# soraduino_lite.net
KiCad netlist of a schematic drawn in EAGLE
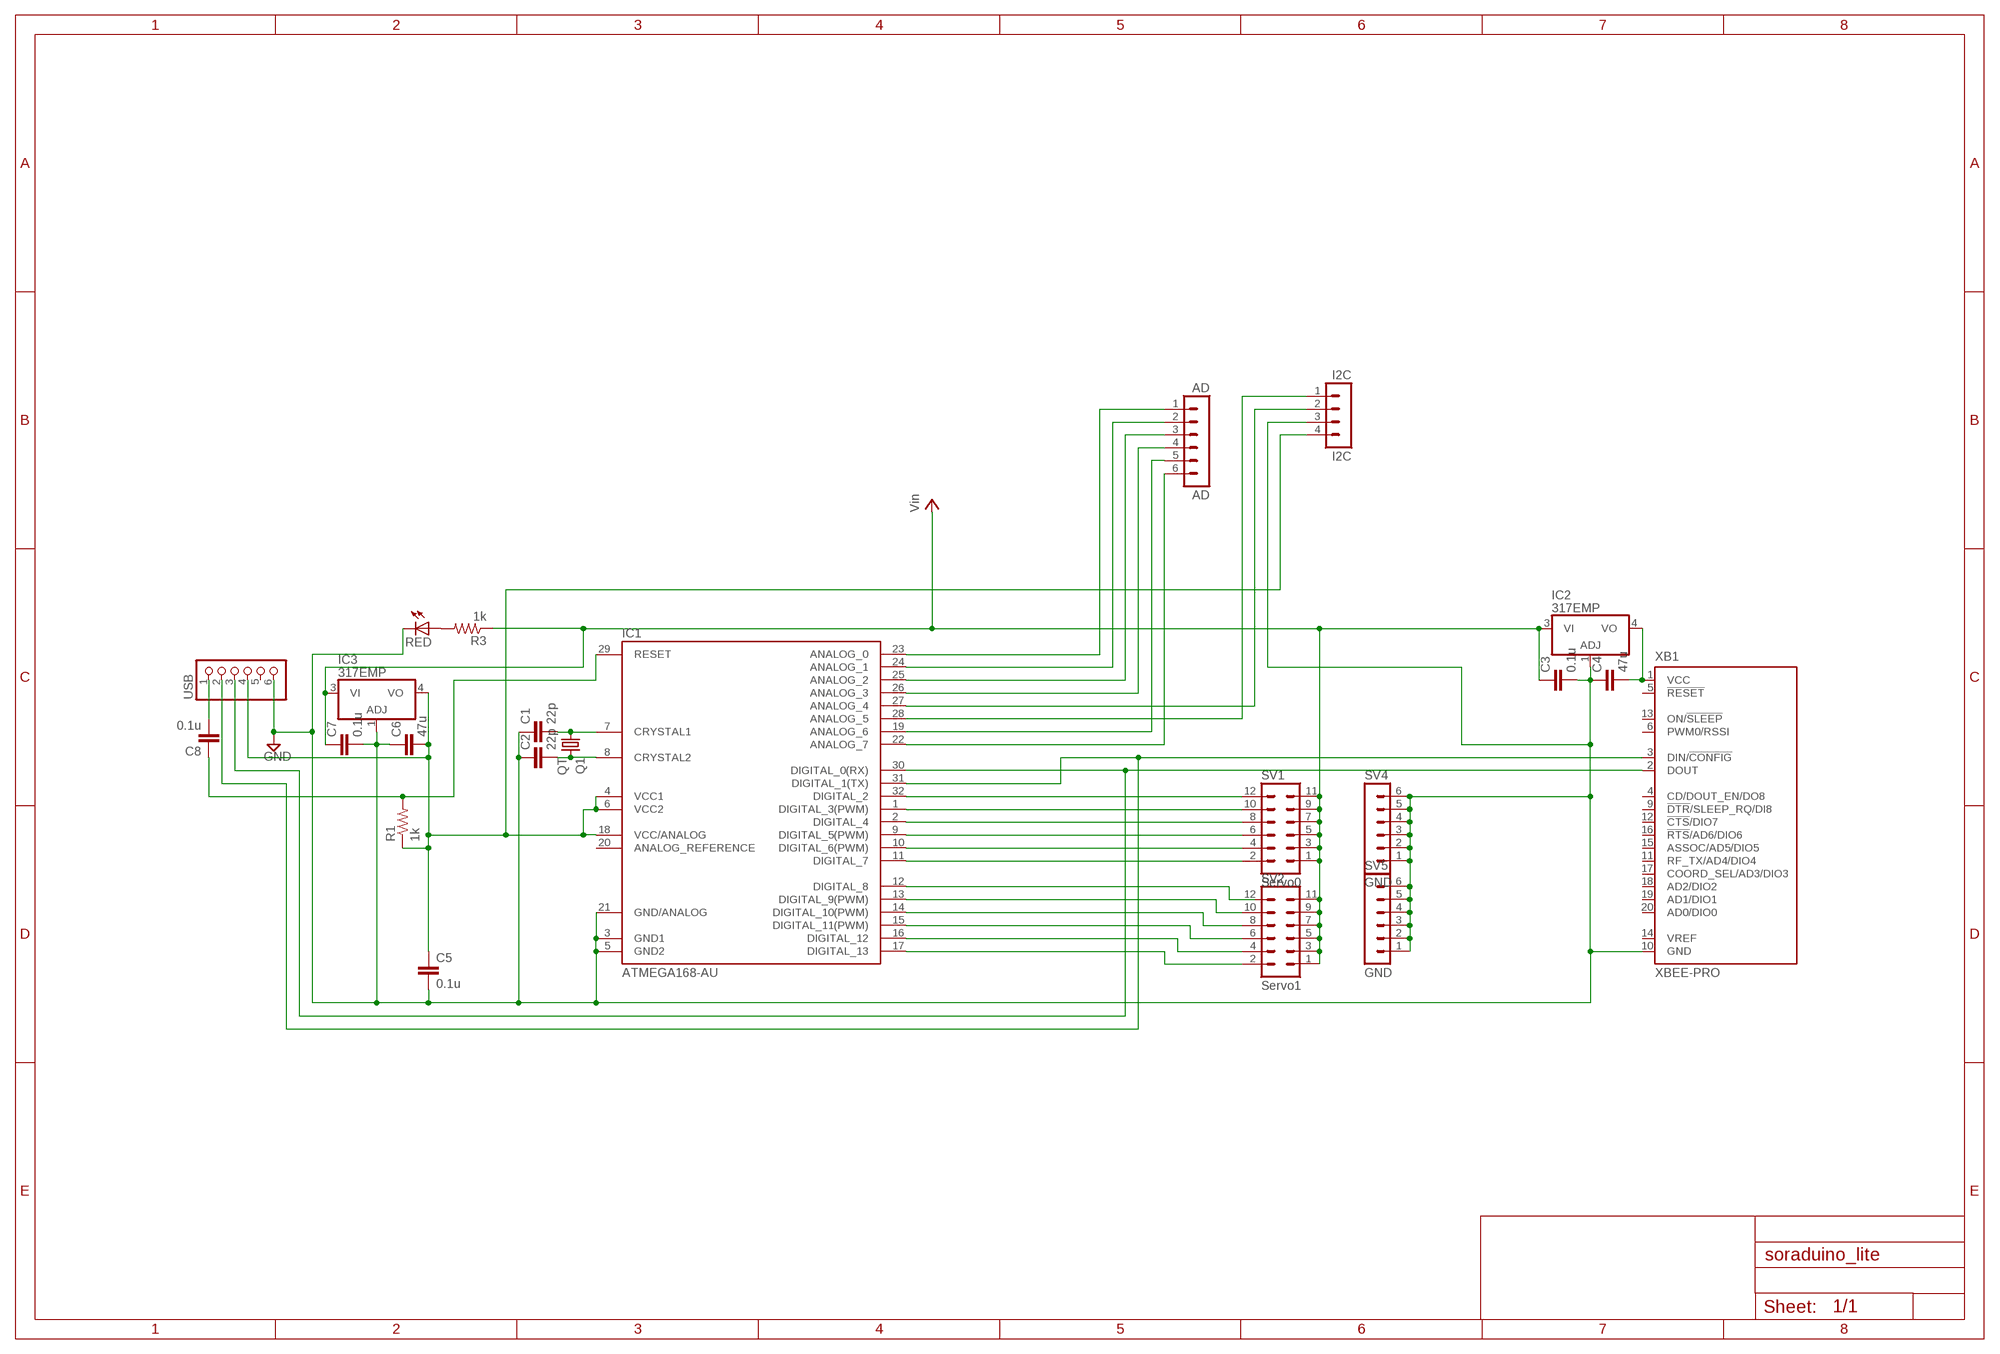
[diagram p0: schematic, sheet 1]

(export (version "E")
  (design (tool "Eeschema 10.0.6"))
  (components
    (comp (ref "AD")
      (value "AD")
      (footprint "eagle-import:MA06-1")
      (libsource (lib "eagle-import") (part "MA06-1"))
    )
    (comp (ref "C1")
      (value "22p")
      (footprint "eagle-import:C050-024X044")
      (libsource (lib "eagle-import") (part "C-EU050-024X044"))
    )
    (comp (ref "C2")
      (value "22p")
      (footprint "eagle-import:C050-024X044")
      (libsource (lib "eagle-import") (part "C-EU050-024X044"))
    )
    (comp (ref "C3")
      (value "0.1u")
      (footprint "eagle-import:C0805K")
      (libsource (lib "eagle-import") (part "resistor_C-EUC0805K"))
    )
    (comp (ref "C4")
      (value "47u")
      (footprint "eagle-import:C0805K")
      (libsource (lib "eagle-import") (part "resistor_C-EUC0805K"))
    )
    (comp (ref "C5")
      (value "0.1u")
      (footprint "eagle-import:C0805K")
      (libsource (lib "eagle-import") (part "resistor_C-EUC0805K"))
    )
    (comp (ref "C6")
      (value "47u")
      (footprint "eagle-import:C0805K")
      (libsource (lib "eagle-import") (part "resistor_C-EUC0805K"))
    )
    (comp (ref "C7")
      (value "0.1u")
      (footprint "eagle-import:C0805K")
      (libsource (lib "eagle-import") (part "resistor_C-EUC0805K"))
    )
    (comp (ref "C8")
      (value "0.1u")
      (footprint "eagle-import:C0805K")
      (libsource (lib "eagle-import") (part "resistor_C-EUC0805K"))
    )
    (comp (ref "I2C")
      (value "I2C")
      (footprint "eagle-import:MA04-1")
      (libsource (lib "eagle-import") (part "MA04-1"))
    )
    (comp (ref "IC1")
      (value "ATMEGA168-AU")
      (footprint "eagle-import:TQFP32-08")
      (libsource (lib "eagle-import") (part "ATMEGA168-AU"))
    )
    (comp (ref "IC2")
      (value "317EMP")
      (footprint "eagle-import:SOT223")
      (libsource (lib "eagle-import") (part "317EMP"))
    )
    (comp (ref "IC3")
      (value "317EMP")
      (footprint "eagle-import:SOT223")
      (libsource (lib "eagle-import") (part "317EMP"))
    )
    (comp (ref "Q1")
      (value "QT")
      (footprint "eagle-import:HC49_S")
      (libsource (lib "eagle-import") (part "CRYSTALHC49S"))
    )
    (comp (ref "R1")
      (value "1k")
      (footprint "eagle-import:R0603")
      (libsource (lib "eagle-import") (part "R-US_R0603"))
    )
    (comp (ref "R3")
      (value "1k")
      (footprint "eagle-import:R0603")
      (libsource (lib "eagle-import") (part "R-US_R0603"))
    )
    (comp (ref "RED")
      (value "LEDCHIPLED_1206")
      (footprint "eagle-import:CHIPLED_1206")
      (libsource (lib "eagle-import") (part "LEDCHIPLED_1206"))
    )
    (comp (ref "SV1")
      (value "Servo0")
      (footprint "eagle-import:MA06-2")
      (libsource (lib "eagle-import") (part "MA06-2"))
    )
    (comp (ref "SV2")
      (value "Servo1")
      (footprint "eagle-import:MA06-2")
      (libsource (lib "eagle-import") (part "MA06-2"))
    )
    (comp (ref "SV4")
      (value "GND")
      (footprint "eagle-import:MA06-1")
      (libsource (lib "eagle-import") (part "MA06-1"))
    )
    (comp (ref "SV5")
      (value "GND")
      (footprint "eagle-import:MA06-1")
      (libsource (lib "eagle-import") (part "MA06-1"))
    )
    (comp (ref "USB")
      (value "PINHD-1X6")
      (footprint "eagle-import:1X06")
      (libsource (lib "eagle-import") (part "PINHD-1X6"))
    )
    (comp (ref "XB1")
      (value "XBEE-PRO")
      (footprint "eagle-import:XBEE-PRO")
      (fields (field (name "MPN") "XBP24-AWI-001"))
      (libsource (lib "eagle-import") (part "XBEE-PRO"))
    )
  )
  (nets
    (net (code "1") (name "GND") (class "Default")
      (node (ref "C1") (pin "1") (pinfunction "1_1") (pintype "passive"))
      (node (ref "C2") (pin "1") (pinfunction "1_1") (pintype "passive"))
      (node (ref "C3") (pin "2") (pinfunction "2_2") (pintype "passive"))
      (node (ref "C4") (pin "1") (pinfunction "1_1") (pintype "passive"))
      (node (ref "C5") (pin "2") (pinfunction "2_2") (pintype "passive"))
      (node (ref "C6") (pin "1") (pinfunction "1_1") (pintype "passive"))
      (node (ref "C7") (pin "2") (pinfunction "2_2") (pintype "passive"))
      (node (ref "I2C") (pin "3") (pinfunction "3_3") (pintype "passive"))
      (node (ref "IC1") (pin "21") (pinfunction "GND/ANALOG_21") (pintype "power_in"))
      (node (ref "IC1") (pin "3") (pinfunction "GND1_3") (pintype "power_in"))
      (node (ref "IC1") (pin "5") (pinfunction "GND2_5") (pintype "power_in"))
      (node (ref "IC2") (pin "1") (pinfunction "ADJ_1") (pintype "input"))
      (node (ref "IC3") (pin "1") (pinfunction "ADJ_1") (pintype "input"))
      (node (ref "RED") (pin "C") (pinfunction "C_C") (pintype "passive"))
      (node (ref "SV4") (pin "1") (pinfunction "1_1") (pintype "passive"))
      (node (ref "SV4") (pin "2") (pinfunction "2_2") (pintype "passive"))
      (node (ref "SV4") (pin "3") (pinfunction "3_3") (pintype "passive"))
      (node (ref "SV4") (pin "4") (pinfunction "4_4") (pintype "passive"))
      (node (ref "SV4") (pin "5") (pinfunction "5_5") (pintype "passive"))
      (node (ref "SV4") (pin "6") (pinfunction "6_6") (pintype "passive"))
      (node (ref "SV5") (pin "1") (pinfunction "1_1") (pintype "passive"))
      (node (ref "SV5") (pin "2") (pinfunction "2_2") (pintype "passive"))
      (node (ref "SV5") (pin "3") (pinfunction "3_3") (pintype "passive"))
      (node (ref "SV5") (pin "4") (pinfunction "4_4") (pintype "passive"))
      (node (ref "SV5") (pin "5") (pinfunction "5_5") (pintype "passive"))
      (node (ref "SV5") (pin "6") (pinfunction "6_6") (pintype "passive"))
      (node (ref "USB") (pin "6") (pinfunction "6_6") (pintype "passive"))
      (node (ref "XB1") (pin "10") (pinfunction "GND_10") (pintype "power_in"))
    )
    (net (code "2") (name "Net-(C8-Pad2)") (class "Default")
      (node (ref "C8") (pin "2") (pinfunction "2_2") (pintype "passive"))
      (node (ref "USB") (pin "1") (pinfunction "1_1") (pintype "passive"))
    )
    (net (code "3") (name "Net-(IC1-ANALOG_0)") (class "Default")
      (node (ref "AD") (pin "1") (pinfunction "1_1") (pintype "passive"))
      (node (ref "IC1") (pin "23") (pinfunction "ANALOG_0_23") (pintype "bidirectional"))
    )
    (net (code "4") (name "Net-(IC1-ANALOG_1)") (class "Default")
      (node (ref "AD") (pin "2") (pinfunction "2_2") (pintype "passive"))
      (node (ref "IC1") (pin "24") (pinfunction "ANALOG_1_24") (pintype "bidirectional"))
    )
    (net (code "5") (name "Net-(IC1-ANALOG_2)") (class "Default")
      (node (ref "AD") (pin "3") (pinfunction "3_3") (pintype "passive"))
      (node (ref "IC1") (pin "25") (pinfunction "ANALOG_2_25") (pintype "bidirectional"))
    )
    (net (code "6") (name "Net-(IC1-ANALOG_3)") (class "Default")
      (node (ref "AD") (pin "4") (pinfunction "4_4") (pintype "passive"))
      (node (ref "IC1") (pin "26") (pinfunction "ANALOG_3_26") (pintype "bidirectional"))
    )
    (net (code "7") (name "Net-(IC1-ANALOG_4)") (class "Default")
      (node (ref "I2C") (pin "2") (pinfunction "2_2") (pintype "passive"))
      (node (ref "IC1") (pin "27") (pinfunction "ANALOG_4_27") (pintype "bidirectional"))
    )
    (net (code "8") (name "Net-(IC1-ANALOG_5)") (class "Default")
      (node (ref "I2C") (pin "1") (pinfunction "1_1") (pintype "passive"))
      (node (ref "IC1") (pin "28") (pinfunction "ANALOG_5_28") (pintype "bidirectional"))
    )
    (net (code "9") (name "Net-(IC1-ANALOG_6)") (class "Default")
      (node (ref "AD") (pin "5") (pinfunction "5_5") (pintype "passive"))
      (node (ref "IC1") (pin "19") (pinfunction "ANALOG_6_19") (pintype "passive"))
    )
    (net (code "10") (name "Net-(IC1-ANALOG_7)") (class "Default")
      (node (ref "AD") (pin "6") (pinfunction "6_6") (pintype "passive"))
      (node (ref "IC1") (pin "22") (pinfunction "ANALOG_7_22") (pintype "passive"))
    )
    (net (code "11") (name "Net-(IC1-CRYSTAL1)") (class "Default")
      (node (ref "C1") (pin "2") (pinfunction "2_2") (pintype "passive"))
      (node (ref "IC1") (pin "7") (pinfunction "CRYSTAL1_7") (pintype "bidirectional"))
      (node (ref "Q1") (pin "1") (pinfunction "1_1") (pintype "passive"))
    )
    (net (code "12") (name "Net-(IC1-CRYSTAL2)") (class "Default")
      (node (ref "C2") (pin "2") (pinfunction "2_2") (pintype "passive"))
      (node (ref "IC1") (pin "8") (pinfunction "CRYSTAL2_8") (pintype "bidirectional"))
      (node (ref "Q1") (pin "2") (pinfunction "2_2") (pintype "passive"))
    )
    (net (code "13") (name "Net-(IC1-DIGITAL_0(RX))") (class "Default")
      (node (ref "IC1") (pin "30") (pinfunction "DIGITAL_0(RX)_30") (pintype "bidirectional"))
      (node (ref "USB") (pin "3") (pinfunction "3_3") (pintype "passive"))
      (node (ref "XB1") (pin "2") (pinfunction "DOUT_2") (pintype "output"))
    )
    (net (code "14") (name "Net-(IC1-DIGITAL_1(TX))") (class "Default")
      (node (ref "IC1") (pin "31") (pinfunction "DIGITAL_1(TX)_31") (pintype "bidirectional"))
      (node (ref "USB") (pin "2") (pinfunction "2_2") (pintype "passive"))
      (node (ref "XB1") (pin "3") (pinfunction "DIN/~{CONFIG}_3") (pintype "input"))
    )
    (net (code "15") (name "Net-(IC1-DIGITAL_2)") (class "Default")
      (node (ref "IC1") (pin "32") (pinfunction "DIGITAL_2_32") (pintype "bidirectional"))
      (node (ref "SV1") (pin "12") (pinfunction "12_12") (pintype "passive"))
    )
    (net (code "16") (name "Net-(IC1-DIGITAL_3(PWM))") (class "Default")
      (node (ref "IC1") (pin "1") (pinfunction "DIGITAL_3(PWM)_1") (pintype "bidirectional"))
      (node (ref "SV1") (pin "10") (pinfunction "10_10") (pintype "passive"))
    )
    (net (code "17") (name "Net-(IC1-DIGITAL_4)") (class "Default")
      (node (ref "IC1") (pin "2") (pinfunction "DIGITAL_4_2") (pintype "bidirectional"))
      (node (ref "SV1") (pin "8") (pinfunction "8_8") (pintype "passive"))
    )
    (net (code "18") (name "Net-(IC1-DIGITAL_5(PWM))") (class "Default")
      (node (ref "IC1") (pin "9") (pinfunction "DIGITAL_5(PWM)_9") (pintype "bidirectional"))
      (node (ref "SV1") (pin "6") (pinfunction "6_6") (pintype "passive"))
    )
    (net (code "19") (name "Net-(IC1-DIGITAL_6(PWM))") (class "Default")
      (node (ref "IC1") (pin "10") (pinfunction "DIGITAL_6(PWM)_10") (pintype "bidirectional"))
      (node (ref "SV1") (pin "4") (pinfunction "4_4") (pintype "passive"))
    )
    (net (code "20") (name "Net-(IC1-DIGITAL_7)") (class "Default")
      (node (ref "IC1") (pin "11") (pinfunction "DIGITAL_7_11") (pintype "bidirectional"))
      (node (ref "SV1") (pin "2") (pinfunction "2_2") (pintype "passive"))
    )
    (net (code "21") (name "Net-(IC1-DIGITAL_9(PWM))") (class "Default")
      (node (ref "IC1") (pin "13") (pinfunction "DIGITAL_9(PWM)_13") (pintype "bidirectional"))
      (node (ref "SV2") (pin "10") (pinfunction "10_10") (pintype "passive"))
    )
    (net (code "22") (name "Net-(IC1-DIGITAL_10(PWM))") (class "Default")
      (node (ref "IC1") (pin "14") (pinfunction "DIGITAL_10(PWM)_14") (pintype "bidirectional"))
      (node (ref "SV2") (pin "8") (pinfunction "8_8") (pintype "passive"))
    )
    (net (code "23") (name "Net-(IC1-DIGITAL_11(PWM))") (class "Default")
      (node (ref "IC1") (pin "15") (pinfunction "DIGITAL_11(PWM)_15") (pintype "bidirectional"))
      (node (ref "SV2") (pin "6") (pinfunction "6_6") (pintype "passive"))
    )
    (net (code "24") (name "Net-(IC1-DIGITAL_12)") (class "Default")
      (node (ref "IC1") (pin "16") (pinfunction "DIGITAL_12_16") (pintype "bidirectional"))
      (node (ref "SV2") (pin "4") (pinfunction "4_4") (pintype "passive"))
    )
    (net (code "25") (name "Net-(IC1-DIGITAL_13)") (class "Default")
      (node (ref "IC1") (pin "17") (pinfunction "DIGITAL_13_17") (pintype "bidirectional"))
      (node (ref "SV2") (pin "2") (pinfunction "2_2") (pintype "passive"))
    )
    (net (code "26") (name "Net-(IC1-RESET)") (class "Default")
      (node (ref "C8") (pin "1") (pinfunction "1_1") (pintype "passive"))
      (node (ref "IC1") (pin "29") (pinfunction "RESET_29") (pintype "bidirectional"))
      (node (ref "R1") (pin "2") (pinfunction "2_2") (pintype "passive"))
    )
    (net (code "27") (name "Net-(IC1-VCC1)") (class "Default")
      (node (ref "C5") (pin "1") (pinfunction "1_1") (pintype "passive"))
      (node (ref "C6") (pin "2") (pinfunction "2_2") (pintype "passive"))
      (node (ref "I2C") (pin "4") (pinfunction "4_4") (pintype "passive"))
      (node (ref "IC1") (pin "18") (pinfunction "VCC/ANALOG_18") (pintype "passive"))
      (node (ref "IC1") (pin "4") (pinfunction "VCC1_4") (pintype "power_in"))
      (node (ref "IC1") (pin "6") (pinfunction "VCC2_6") (pintype "power_in"))
      (node (ref "IC3") (pin "4") (pinfunction "VO_4") (pintype "passive"))
      (node (ref "R1") (pin "1") (pinfunction "1_1") (pintype "passive"))
      (node (ref "USB") (pin "4") (pinfunction "4_4") (pintype "passive"))
    )
    (net (code "28") (name "Net-(IC2-VO)") (class "Default")
      (node (ref "C4") (pin "2") (pinfunction "2_2") (pintype "passive"))
      (node (ref "IC2") (pin "4") (pinfunction "VO_4") (pintype "passive"))
      (node (ref "XB1") (pin "1") (pinfunction "VCC_1") (pintype "power_in"))
    )
    (net (code "29") (name "Net-(R3-Pad2)") (class "Default")
      (node (ref "R3") (pin "2") (pinfunction "2_2") (pintype "passive"))
      (node (ref "RED") (pin "A") (pinfunction "A_A") (pintype "passive"))
    )
    (net (code "30") (name "Vin") (class "Default")
      (node (ref "C3") (pin "1") (pinfunction "1_1") (pintype "passive"))
      (node (ref "C7") (pin "1") (pinfunction "1_1") (pintype "passive"))
      (node (ref "IC2") (pin "3") (pinfunction "VI_3") (pintype "input"))
      (node (ref "IC3") (pin "3") (pinfunction "VI_3") (pintype "input"))
      (node (ref "R3") (pin "1") (pinfunction "1_1") (pintype "passive"))
      (node (ref "SV1") (pin "1") (pinfunction "1_1") (pintype "passive"))
      (node (ref "SV1") (pin "11") (pinfunction "11_11") (pintype "passive"))
      (node (ref "SV1") (pin "3") (pinfunction "3_3") (pintype "passive"))
      (node (ref "SV1") (pin "5") (pinfunction "5_5") (pintype "passive"))
      (node (ref "SV1") (pin "7") (pinfunction "7_7") (pintype "passive"))
      (node (ref "SV1") (pin "9") (pinfunction "9_9") (pintype "passive"))
      (node (ref "SV2") (pin "1") (pinfunction "1_1") (pintype "passive"))
      (node (ref "SV2") (pin "11") (pinfunction "11_11") (pintype "passive"))
      (node (ref "SV2") (pin "3") (pinfunction "3_3") (pintype "passive"))
      (node (ref "SV2") (pin "5") (pinfunction "5_5") (pintype "passive"))
      (node (ref "SV2") (pin "7") (pinfunction "7_7") (pintype "passive"))
      (node (ref "SV2") (pin "9") (pinfunction "9_9") (pintype "passive"))
    )
    (net (code "31") (name "unconnected-(IC1-ANALOG_REFERENCE-Pad20)") (class "Default")
      (node (ref "IC1") (pin "20") (pinfunction "ANALOG_REFERENCE_20") (pintype "passive"))
    )
    (net (code "32") (name "unconnected-(IC1-DIGITAL_8-Pad12)") (class "Default")
      (node (ref "IC1") (pin "12") (pinfunction "DIGITAL_8_12") (pintype "bidirectional"))
    )
    (net (code "33") (name "unconnected-(SV2-Pad12)") (class "Default")
      (node (ref "SV2") (pin "12") (pinfunction "12_12") (pintype "passive"))
    )
    (net (code "34") (name "unconnected-(USB-Pad5)") (class "Default")
      (node (ref "USB") (pin "5") (pinfunction "5_5") (pintype "passive"))
    )
    (net (code "35") (name "unconnected-(XB1-AD0{slash}DIO0-Pad20)") (class "Default")
      (node (ref "XB1") (pin "20") (pinfunction "AD0/DIO0_20") (pintype "bidirectional"))
    )
    (net (code "36") (name "unconnected-(XB1-AD1{slash}DIO1-Pad19)") (class "Default")
      (node (ref "XB1") (pin "19") (pinfunction "AD1/DIO1_19") (pintype "bidirectional"))
    )
    (net (code "37") (name "unconnected-(XB1-AD2{slash}DIO2-Pad18)") (class "Default")
      (node (ref "XB1") (pin "18") (pinfunction "AD2/DIO2_18") (pintype "bidirectional"))
    )
    (net (code "38") (name "unconnected-(XB1-ASSOC{slash}AD5{slash}DIO5-Pad15)") (class "Default")
      (node (ref "XB1") (pin "15") (pinfunction "ASSOC/AD5/DIO5_15") (pintype "bidirectional"))
    )
    (net (code "39") (name "unconnected-(XB1-CD{slash}DOUT_EN{slash}DO8-Pad4)") (class "Default")
      (node (ref "XB1") (pin "4") (pinfunction "CD/DOUT_EN/DO8_4") (pintype "output"))
    )
    (net (code "40") (name "unconnected-(XB1-COORD_SEL{slash}AD3{slash}DIO3-Pad17)") (class "Default")
      (node (ref "XB1") (pin "17") (pinfunction "COORD_SEL/AD3/DIO3_17") (pintype "bidirectional"))
    )
    (net (code "41") (name "unconnected-(XB1-ON{slash}~{SLEEP}-Pad13)") (class "Default")
      (node (ref "XB1") (pin "13") (pinfunction "ON/~{SLEEP}_13") (pintype "output"))
    )
    (net (code "42") (name "unconnected-(XB1-PWM0{slash}RSSI-Pad6)") (class "Default")
      (node (ref "XB1") (pin "6") (pinfunction "PWM0/RSSI_6") (pintype "output"))
    )
    (net (code "43") (name "unconnected-(XB1-RF_TX{slash}AD4{slash}DIO4-Pad11)") (class "Default")
      (node (ref "XB1") (pin "11") (pinfunction "RF_TX/AD4/DIO4_11") (pintype "bidirectional"))
    )
    (net (code "44") (name "unconnected-(XB1-VREF-Pad14)") (class "Default")
      (node (ref "XB1") (pin "14") (pinfunction "VREF_14") (pintype "input"))
    )
    (net (code "45") (name "unconnected-(XB1-~{CTS}{slash}DIO7-Pad12)") (class "Default")
      (node (ref "XB1") (pin "12") (pinfunction "~{CTS}/DIO7_12") (pintype "bidirectional"))
    )
    (net (code "46") (name "unconnected-(XB1-~{DTR}{slash}SLEEP_RQ{slash}DI8-Pad9)") (class "Default")
      (node (ref "XB1") (pin "9") (pinfunction "~{DTR}/SLEEP_RQ/DI8_9") (pintype "bidirectional"))
    )
    (net (code "47") (name "unconnected-(XB1-~{RESET}-Pad5)") (class "Default")
      (node (ref "XB1") (pin "5") (pinfunction "~{RESET}_5") (pintype "input"))
    )
    (net (code "48") (name "unconnected-(XB1-~{RTS}{slash}AD6{slash}DIO6-Pad16)") (class "Default")
      (node (ref "XB1") (pin "16") (pinfunction "~{RTS}/AD6/DIO6_16") (pintype "bidirectional"))
    )
  )
)
